# 01_FPGA_FlashMem.net
KiCad netlist of a schematic drawn in Altium Designer
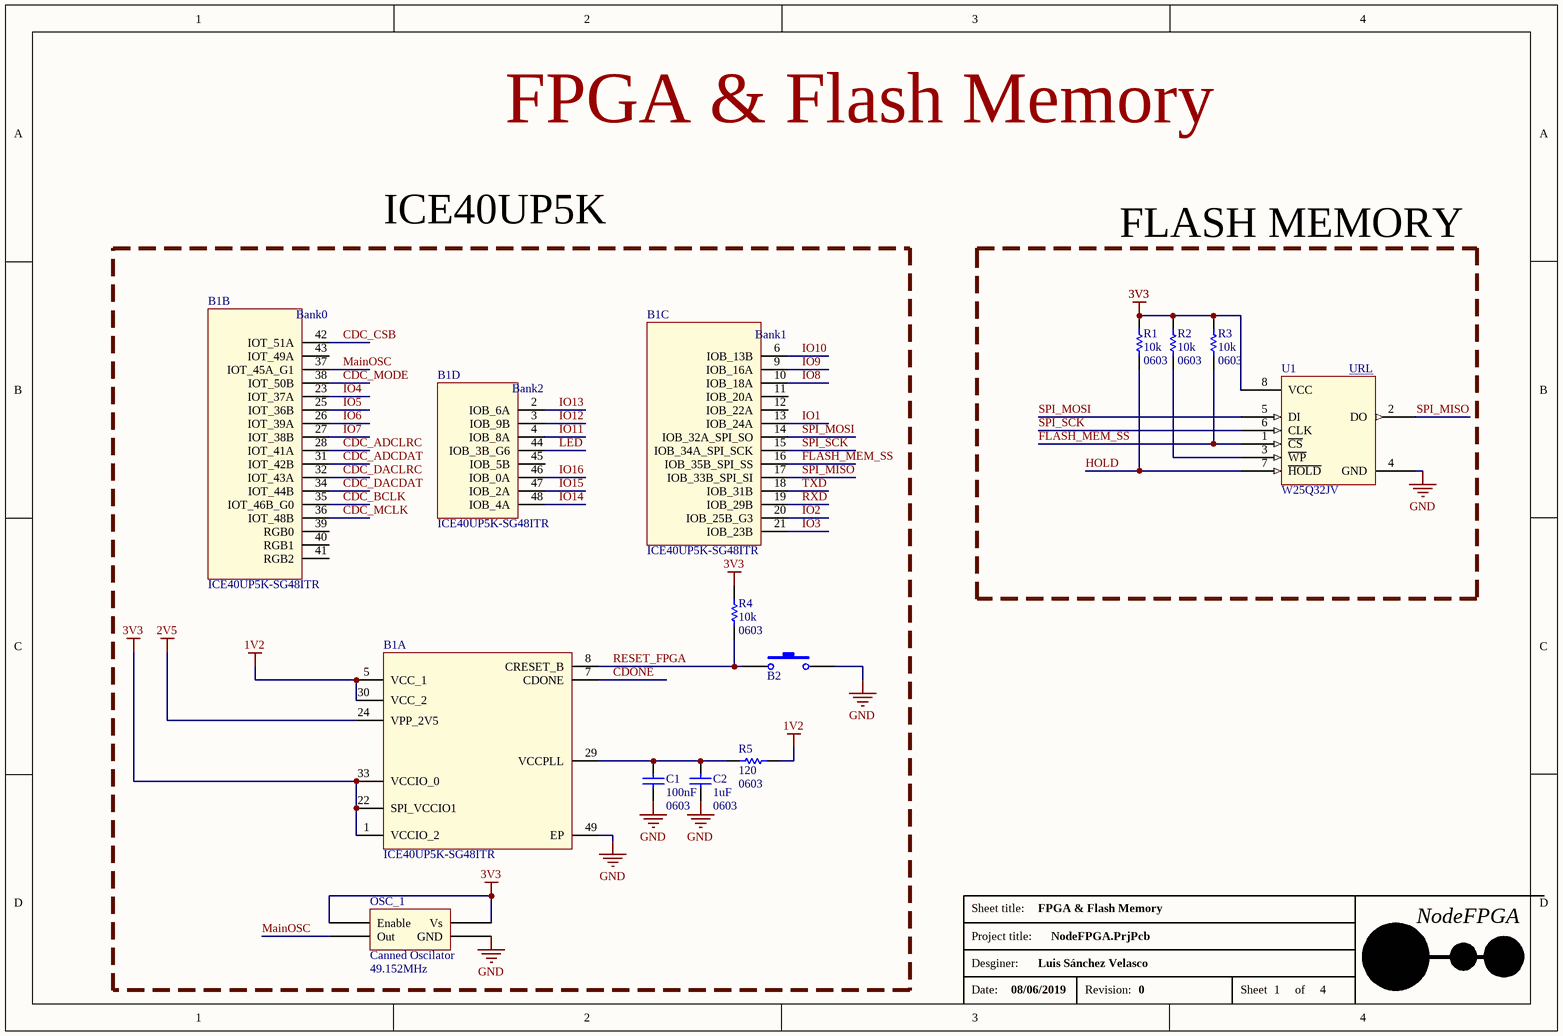
[diagram p0: 01_FPGA_FlashMem.SchDoc]

(export (version "E")
  (design (tool "Eeschema 10.0.6"))
  (components
    (comp (ref "B1")
      (value "ICE40UP5K-SG48ITR")
      (footprint "QFN50P700X700X100-49N-D")
      (description "FPGA - Field Programmable Gate Array iCE40-UltraPlus, 5280 LUTs, 1.2V")
      (fields (field (name "MOUSER PART NUMBER") "842-40UP5KSG48ITR"))
      (libsource (lib "NodeFPGA") (part "ICE40UP5K-SG48ITR"))
    )
    (comp (ref "B2")
      (value "FSM6JH")
      (footprint "SMD_PUSHBUTTON_3x6x2mm5")
      (description "Button THT Switch")
      (libsource (lib "NodeFPGA") (part "FSM6JH"))
    )
    (comp (ref "C1")
      (value "100nF")
      (footprint "0603 CAP")
      (description "Capacitor")
      (fields (field (name "PACKAGE") "0603") (field (name "Comment") "Ceramic capacitor"))
      (libsource (lib "NodeFPGA") (part "Capacitor"))
    )
    (comp (ref "C2")
      (value "1uF")
      (footprint "0603 CAP")
      (description "Capacitor")
      (fields (field (name "PACKAGE") "0603") (field (name "Comment") "Ceramic capacitor"))
      (libsource (lib "NodeFPGA") (part "Capacitor"))
    )
    (comp (ref "OSC_1")
      (value "Canned Oscilator")
      (footprint "Canned Oscilator")
      (description "Canned Oscilator -LFSPXO019116BULK")
      (fields (field (name "ALTIUM_VALUE") "49.152MHz"))
      (libsource (lib "NodeFPGA") (part "Canned Oscilator"))
    )
    (comp (ref "R1")
      (value "10k")
      (footprint "Resistencia 0603")
      (description "Resistor")
      (fields (field (name "PACKAGE") "0603"))
      (libsource (lib "NodeFPGA") (part "Resistor"))
    )
    (comp (ref "R2")
      (value "10k")
      (footprint "Resistencia 0603")
      (description "Resistor")
      (fields (field (name "PACKAGE") "0603"))
      (libsource (lib "NodeFPGA") (part "Resistor"))
    )
    (comp (ref "R3")
      (value "10k")
      (footprint "Resistencia 0603")
      (description "Resistor")
      (fields (field (name "PACKAGE") "0603"))
      (libsource (lib "NodeFPGA") (part "Resistor"))
    )
    (comp (ref "R4")
      (value "10k")
      (footprint "Resistencia 0603")
      (description "Resistor")
      (fields (field (name "PACKAGE") "0603"))
      (libsource (lib "NodeFPGA") (part "Resistor"))
    )
    (comp (ref "R5")
      (value "120")
      (footprint "Resistencia 0603")
      (description "Resistor")
      (fields (field (name "PACKAGE") "0603"))
      (libsource (lib "NodeFPGA") (part "Resistor"))
    )
    (comp (ref "U1")
      (value "W25Q32JV")
      (footprint "W25Q32J")
      (description "32M-BIT SERIAL FLASH MEMORY WITH DUAL AND QUAD SPI")
      (libsource (lib "NodeFPGA") (part "W25Q32JV"))
    )
  )
  (nets
    (net (code "1") (name "/CDC_ADCDAT") (class "Default")
      (node (ref "B1") (pin "31") (pinfunction "IOT_42B_31") (pintype "passive"))
    )
    (net (code "2") (name "/CDC_ADCLRC") (class "Default")
      (node (ref "B1") (pin "28") (pinfunction "IOT_41A_28") (pintype "passive"))
    )
    (net (code "3") (name "/CDC_BCLK") (class "Default")
      (node (ref "B1") (pin "35") (pinfunction "IOT_46B_G0_35") (pintype "passive"))
    )
    (net (code "4") (name "/CDC_CSB") (class "Default")
      (node (ref "B1") (pin "42") (pinfunction "IOT_51A_42") (pintype "passive"))
    )
    (net (code "5") (name "/CDC_DACDAT") (class "Default")
      (node (ref "B1") (pin "34") (pinfunction "IOT_44B_34") (pintype "passive"))
    )
    (net (code "6") (name "/CDC_DACLRC") (class "Default")
      (node (ref "B1") (pin "32") (pinfunction "IOT_43A_32") (pintype "passive"))
    )
    (net (code "7") (name "/CDC_MCLK") (class "Default")
      (node (ref "B1") (pin "36") (pinfunction "IOT_48B_36") (pintype "passive"))
    )
    (net (code "8") (name "/CDC_MODE") (class "Default")
      (node (ref "B1") (pin "38") (pinfunction "IOT_50B_38") (pintype "passive"))
    )
    (net (code "9") (name "/CDONE") (class "Default")
      (node (ref "B1") (pin "7") (pinfunction "CDONE_7") (pintype "passive"))
    )
    (net (code "10") (name "/FLASH_MEM_SS") (class "Default")
      (node (ref "B1") (pin "16") (pinfunction "IOB_35B_SPI_SS_16") (pintype "passive"))
      (node (ref "R3") (pin "1") (pinfunction "1_1") (pintype "passive"))
      (node (ref "U1") (pin "1") (pinfunction "~{CS}_1") (pintype "input"))
    )
    (net (code "11") (name "/HOLD") (class "Default")
      (node (ref "R1") (pin "1") (pinfunction "1_1") (pintype "passive"))
      (node (ref "U1") (pin "7") (pinfunction "~{HOLD}_7") (pintype "input"))
    )
    (net (code "12") (name "/IO1") (class "Default")
      (node (ref "B1") (pin "13") (pinfunction "IOB_24A_13") (pintype "passive"))
    )
    (net (code "13") (name "/IO2") (class "Default")
      (node (ref "B1") (pin "20") (pinfunction "IOB_25B_G3_20") (pintype "passive"))
    )
    (net (code "14") (name "/IO3") (class "Default")
      (node (ref "B1") (pin "21") (pinfunction "IOB_23B_21") (pintype "passive"))
    )
    (net (code "15") (name "/IO4") (class "Default")
      (node (ref "B1") (pin "23") (pinfunction "IOT_37A_23") (pintype "passive"))
    )
    (net (code "16") (name "/IO5") (class "Default")
      (node (ref "B1") (pin "25") (pinfunction "IOT_36B_25") (pintype "passive"))
    )
    (net (code "17") (name "/IO6") (class "Default")
      (node (ref "B1") (pin "26") (pinfunction "IOT_39A_26") (pintype "passive"))
    )
    (net (code "18") (name "/IO7") (class "Default")
      (node (ref "B1") (pin "27") (pinfunction "IOT_38B_27") (pintype "passive"))
    )
    (net (code "19") (name "/IO8") (class "Default")
      (node (ref "B1") (pin "10") (pinfunction "IOB_18A_10") (pintype "passive"))
    )
    (net (code "20") (name "/IO9") (class "Default")
      (node (ref "B1") (pin "9") (pinfunction "IOB_16A_9") (pintype "passive"))
    )
    (net (code "21") (name "/IO10") (class "Default")
      (node (ref "B1") (pin "6") (pinfunction "IOB_13B_6") (pintype "passive"))
    )
    (net (code "22") (name "/IO11") (class "Default")
      (node (ref "B1") (pin "4") (pinfunction "IOB_8A_4") (pintype "passive"))
    )
    (net (code "23") (name "/IO12") (class "Default")
      (node (ref "B1") (pin "3") (pinfunction "IOB_9B_3") (pintype "passive"))
    )
    (net (code "24") (name "/IO13") (class "Default")
      (node (ref "B1") (pin "2") (pinfunction "IOB_6A_2") (pintype "passive"))
    )
    (net (code "25") (name "/IO14") (class "Default")
      (node (ref "B1") (pin "48") (pinfunction "IOB_4A_48") (pintype "passive"))
    )
    (net (code "26") (name "/IO15") (class "Default")
      (node (ref "B1") (pin "47") (pinfunction "IOB_2A_47") (pintype "passive"))
    )
    (net (code "27") (name "/IO16") (class "Default")
      (node (ref "B1") (pin "46") (pinfunction "IOB_0A_46") (pintype "passive"))
    )
    (net (code "28") (name "/LED") (class "Default")
      (node (ref "B1") (pin "44") (pinfunction "IOB_3B_G6_44") (pintype "passive"))
    )
    (net (code "29") (name "/MainOSC") (class "Default")
      (node (ref "B1") (pin "37") (pinfunction "IOT_45A_G1_37") (pintype "passive"))
      (node (ref "OSC_1") (pin "3") (pinfunction "Out_3") (pintype "passive"))
    )
    (net (code "30") (name "/RESET_FPGA") (class "Default")
      (node (ref "B1") (pin "8") (pinfunction "CRESET_B_8") (pintype "passive"))
      (node (ref "B2") (pin "1") (pinfunction "1_1") (pintype "passive"))
      (node (ref "R4") (pin "1") (pinfunction "1_1") (pintype "passive"))
    )
    (net (code "31") (name "/RXD") (class "Default")
      (node (ref "B1") (pin "19") (pinfunction "IOB_29B_19") (pintype "passive"))
    )
    (net (code "32") (name "/SPI_MISO") (class "Default")
      (node (ref "B1") (pin "17") (pinfunction "IOB_33B_SPI_SI_17") (pintype "passive"))
      (node (ref "U1") (pin "2") (pinfunction "DO_2") (pintype "output"))
    )
    (net (code "33") (name "/SPI_MOSI") (class "Default")
      (node (ref "B1") (pin "14") (pinfunction "IOB_32A_SPI_SO_14") (pintype "passive"))
      (node (ref "U1") (pin "5") (pinfunction "DI_5") (pintype "input"))
    )
    (net (code "34") (name "/SPI_SCK") (class "Default")
      (node (ref "B1") (pin "15") (pinfunction "IOB_34A_SPI_SCK_15") (pintype "passive"))
      (node (ref "U1") (pin "6") (pinfunction "CLK_6") (pintype "input"))
    )
    (net (code "35") (name "/TXD") (class "Default")
      (node (ref "B1") (pin "18") (pinfunction "IOB_31B_18") (pintype "passive"))
    )
    (net (code "36") (name "1V2") (class "Default")
      (node (ref "B1") (pin "30") (pinfunction "VCC_2_30") (pintype "passive"))
      (node (ref "B1") (pin "5") (pinfunction "VCC_1_5") (pintype "passive"))
      (node (ref "R5") (pin "2") (pinfunction "2_2") (pintype "passive"))
    )
    (net (code "37") (name "2V5") (class "Default")
      (node (ref "B1") (pin "24") (pinfunction "VPP_2V5_24") (pintype "passive"))
    )
    (net (code "38") (name "3V3") (class "Default")
      (node (ref "B1") (pin "1") (pinfunction "VCCIO_2_1") (pintype "passive"))
      (node (ref "B1") (pin "22") (pinfunction "SPI_VCCIO1_22") (pintype "passive"))
      (node (ref "B1") (pin "33") (pinfunction "VCCIO_0_33") (pintype "passive"))
      (node (ref "OSC_1") (pin "1") (pinfunction "Enable_1") (pintype "passive"))
      (node (ref "OSC_1") (pin "4") (pinfunction "Vs_4") (pintype "passive"))
      (node (ref "R1") (pin "2") (pinfunction "2_2") (pintype "passive"))
      (node (ref "R2") (pin "2") (pinfunction "2_2") (pintype "passive"))
      (node (ref "R3") (pin "2") (pinfunction "2_2") (pintype "passive"))
      (node (ref "R4") (pin "2") (pinfunction "2_2") (pintype "passive"))
      (node (ref "U1") (pin "8") (pinfunction "VCC_8") (pintype "power_in"))
    )
    (net (code "39") (name "GND") (class "Default")
      (node (ref "B1") (pin "49") (pinfunction "EP_49") (pintype "passive"))
      (node (ref "B2") (pin "2") (pinfunction "2_2") (pintype "passive"))
      (node (ref "C1") (pin "1") (pinfunction "1_1") (pintype "passive"))
      (node (ref "C2") (pin "1") (pinfunction "1_1") (pintype "passive"))
      (node (ref "OSC_1") (pin "2") (pinfunction "GND_2") (pintype "passive"))
      (node (ref "U1") (pin "4") (pinfunction "GND_4") (pintype "power_in"))
    )
    (net (code "40") (name "Net-(B1A-VCCPLL)") (class "Default")
      (node (ref "B1") (pin "29") (pinfunction "VCCPLL_29") (pintype "passive"))
      (node (ref "C1") (pin "2") (pinfunction "2_2") (pintype "passive"))
      (node (ref "C2") (pin "2") (pinfunction "2_2") (pintype "passive"))
      (node (ref "R5") (pin "1") (pinfunction "1_1") (pintype "passive"))
    )
    (net (code "41") (name "Net-(U1-~{WP})") (class "Default")
      (node (ref "R2") (pin "1") (pinfunction "1_1") (pintype "passive"))
      (node (ref "U1") (pin "3") (pinfunction "~{WP}_3") (pintype "input"))
    )
    (net (code "42") (name "unconnected-(B1B-IOT_49A-Pad43)") (class "Default")
      (node (ref "B1") (pin "43") (pinfunction "IOT_49A_43") (pintype "passive"))
    )
    (net (code "43") (name "unconnected-(B1B-RGB0-Pad39)") (class "Default")
      (node (ref "B1") (pin "39") (pinfunction "RGB0_39") (pintype "passive"))
    )
    (net (code "44") (name "unconnected-(B1B-RGB1-Pad40)") (class "Default")
      (node (ref "B1") (pin "40") (pinfunction "RGB1_40") (pintype "passive"))
    )
    (net (code "45") (name "unconnected-(B1B-RGB2-Pad41)") (class "Default")
      (node (ref "B1") (pin "41") (pinfunction "RGB2_41") (pintype "passive"))
    )
    (net (code "46") (name "unconnected-(B1C-IOB_20A-Pad11)") (class "Default")
      (node (ref "B1") (pin "11") (pinfunction "IOB_20A_11") (pintype "passive"))
    )
    (net (code "47") (name "unconnected-(B1C-IOB_22A-Pad12)") (class "Default")
      (node (ref "B1") (pin "12") (pinfunction "IOB_22A_12") (pintype "passive"))
    )
    (net (code "48") (name "unconnected-(B1D-IOB_5B-Pad45)") (class "Default")
      (node (ref "B1") (pin "45") (pinfunction "IOB_5B_45") (pintype "passive"))
    )
  )
)
